# POWER-SUPPLY.net
KiCad netlist of a schematic drawn in Altium Designer
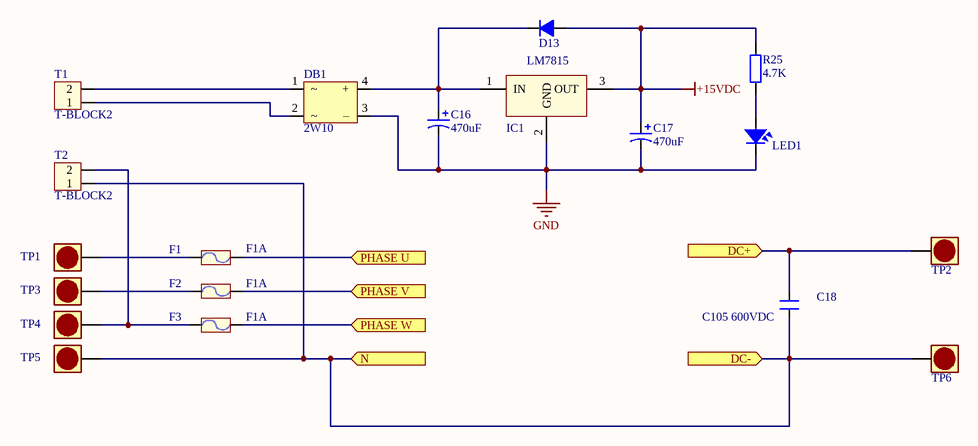
[diagram p0: POWER-SUPPLY.SchDoc]

(export (version "E")
  (design (tool "Eeschema 10.0.6"))
  (components
    (comp (ref "C16")
      (value "470uF")
      (footprint "C6mm")
      (description "CAP-Radial")
      (fields (field (name "PUBLISHER") "Altium Limited"))
      (libsource (lib "Sang_Library") (part "CAP-Radial"))
    )
    (comp (ref "C17")
      (value "470uF")
      (footprint "C6mm")
      (description "CAP-Radial")
      (fields (field (name "PUBLISHER") "Altium Limited"))
      (libsource (lib "Sang_Library") (part "CAP-Radial"))
    )
    (comp (ref "C18")
      (value "C105 600VDC")
      (footprint "CAP-POLY-25mm")
      (description "CAP-POLY")
      (libsource (lib "Sang_Library") (part "CAP-POLY"))
    )
    (comp (ref "D13")
      (value "Diode  1N4007")
      (footprint "DO41-1A")
      (description "Diode 1A")
      (libsource (lib "Sang_Library") (part "Diode  1N4007"))
    )
    (comp (ref "DB1")
      (value "2W10")
      (footprint "DB-2W10")
      (libsource (lib "Sang_Library") (part "DIODE BRIDGE1"))
    )
    (comp (ref "F1")
      (value "F1A")
      (footprint "Fuse")
      (description "Fuse")
      (fields (field (name "DESIGNED BY") "VanDungEvn"))
      (libsource (lib "syhaunguyen") (part "Fuse"))
    )
    (comp (ref "F2")
      (value "F1A")
      (footprint "Fuse")
      (description "Fuse")
      (fields (field (name "DESIGNED BY") "VanDungEvn"))
      (libsource (lib "syhaunguyen") (part "Fuse"))
    )
    (comp (ref "F3")
      (value "F1A")
      (footprint "Fuse")
      (description "Fuse")
      (fields (field (name "DESIGNED BY") "VanDungEvn"))
      (libsource (lib "syhaunguyen") (part "Fuse"))
    )
    (comp (ref "IC1")
      (value "LM7815")
      (footprint "QTO-220")
      (description "On ap +, from + 5 to + 24VDC")
      (libsource (lib "Sang_Library") (part "LM78xx"))
    )
    (comp (ref "LED1")
      (value "LED")
      (footprint "LED-5-BLUE")
      (description "LED Single colour Green and Red")
      (libsource (lib "Sang_Library") (part "LED"))
    )
    (comp (ref "R25")
      (value "4.7K")
      (footprint "R1/4W")
      (description "Resistor 1/4W")
      (libsource (lib "Sang_Library") (part "R1/4W"))
    )
    (comp (ref "T1")
      (value "T-BLOCK2")
      (footprint "T-2EDGV-5.08- 2P")
      (description "T-BLOCK2(Green)")
      (libsource (lib "Sang_Library") (part "T-BLOCK2"))
    )
    (comp (ref "T2")
      (value "T-BLOCK2")
      (footprint "T-2EDGV-5.08- 2P")
      (description "T-BLOCK2(Green)")
      (libsource (lib "Sang_Library") (part "T-BLOCK2"))
    )
    (comp (ref "TP1") (value "JP1P") (footprint "PW-JP") (libsource (lib "Huan") (part "JP1P")))
    (comp (ref "TP2") (value "JP1P") (footprint "PW-JP") (libsource (lib "") (part "JP1P_1")))
    (comp (ref "TP3") (value "JP1P") (footprint "PW-JP") (libsource (lib "Huan") (part "JP1P")))
    (comp (ref "TP4") (value "JP1P") (footprint "PW-JP") (libsource (lib "Huan") (part "JP1P")))
    (comp (ref "TP5") (value "JP1P") (footprint "PW-JP") (libsource (lib "Huan") (part "JP1P")))
    (comp (ref "TP6") (value "JP1P") (footprint "PW-JP") (libsource (lib "") (part "JP1P_1")))
  )
  (nets
    (net (code "1") (name "+15VDC") (class "Default")
      (node (ref "C17") (pin "1") (pinfunction "1_1") (pintype "passive"))
      (node (ref "D13") (pin "1") (pinfunction "1_1") (pintype "passive"))
      (node (ref "IC1") (pin "3") (pinfunction "OUT_3") (pintype "passive"))
      (node (ref "R25") (pin "2") (pinfunction "2_2") (pintype "passive"))
    )
    (net (code "2") (name "/DC+") (class "Default")
      (node (ref "C18") (pin "2") (pinfunction "2_2") (pintype "passive"))
      (node (ref "TP2") (pin "1") (pinfunction "1_1") (pintype "passive"))
    )
    (net (code "3") (name "/DC-") (class "Default")
      (node (ref "C18") (pin "1") (pinfunction "1_1") (pintype "passive"))
      (node (ref "T2") (pin "1") (pinfunction "1_1") (pintype "passive"))
      (node (ref "TP5") (pin "1") (pinfunction "1_1") (pintype "passive"))
      (node (ref "TP6") (pin "1") (pinfunction "1_1") (pintype "passive"))
    )
    (net (code "4") (name "/PHASE U") (class "Default")
      (node (ref "F1") (pin "2") (pinfunction "2_2") (pintype "passive"))
    )
    (net (code "5") (name "/PHASE V") (class "Default")
      (node (ref "F2") (pin "2") (pinfunction "2_2") (pintype "passive"))
    )
    (net (code "6") (name "/PHASE W") (class "Default")
      (node (ref "F3") (pin "2") (pinfunction "2_2") (pintype "passive"))
    )
    (net (code "7") (name "GND") (class "Default")
      (node (ref "C16") (pin "2") (pinfunction "2_2") (pintype "passive"))
      (node (ref "C17") (pin "2") (pinfunction "2_2") (pintype "passive"))
      (node (ref "DB1") (pin "3") (pinfunction "–_3") (pintype "passive"))
      (node (ref "IC1") (pin "2") (pinfunction "GND_2") (pintype "passive"))
      (node (ref "LED1") (pin "2") (pinfunction "2_2") (pintype "passive"))
    )
    (net (code "8") (name "Net-(DB1-+)") (class "Default")
      (node (ref "C16") (pin "1") (pinfunction "1_1") (pintype "passive"))
      (node (ref "D13") (pin "2") (pinfunction "2_2") (pintype "passive"))
      (node (ref "DB1") (pin "4") (pinfunction "+_4") (pintype "passive"))
      (node (ref "IC1") (pin "1") (pinfunction "IN_1") (pintype "passive"))
    )
    (net (code "9") (name "Net-(DB1-~-Pad1)") (class "Default")
      (node (ref "DB1") (pin "1") (pinfunction "~_1") (pintype "passive"))
      (node (ref "T1") (pin "2") (pinfunction "2_2") (pintype "passive"))
    )
    (net (code "10") (name "Net-(DB1-~-Pad2)") (class "Default")
      (node (ref "DB1") (pin "2") (pinfunction "~_2") (pintype "passive"))
      (node (ref "T1") (pin "1") (pinfunction "1_1") (pintype "passive"))
    )
    (net (code "11") (name "Net-(F1-Pad1)") (class "Default")
      (node (ref "F1") (pin "1") (pinfunction "1_1") (pintype "passive"))
      (node (ref "TP1") (pin "1") (pinfunction "1_1") (pintype "passive"))
    )
    (net (code "12") (name "Net-(F2-Pad1)") (class "Default")
      (node (ref "F2") (pin "1") (pinfunction "1_1") (pintype "passive"))
      (node (ref "TP3") (pin "1") (pinfunction "1_1") (pintype "passive"))
    )
    (net (code "13") (name "Net-(F3-Pad1)") (class "Default")
      (node (ref "F3") (pin "1") (pinfunction "1_1") (pintype "passive"))
      (node (ref "T2") (pin "2") (pinfunction "2_2") (pintype "passive"))
      (node (ref "TP4") (pin "1") (pinfunction "1_1") (pintype "passive"))
    )
    (net (code "14") (name "Net-(LED1-Pad1)") (class "Default")
      (node (ref "LED1") (pin "1") (pinfunction "1_1") (pintype "passive"))
      (node (ref "R25") (pin "1") (pinfunction "1_1") (pintype "passive"))
    )
  )
)
